# MCISO-S02-V00-PSU5VA.net
KiCad netlist of a schematic drawn in Altium Designer
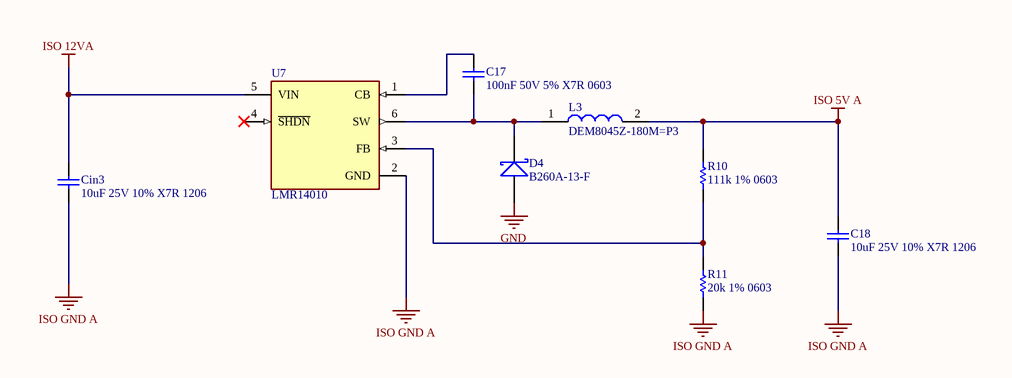
[diagram p0: MCISO-S02-V00-PSU5VA.SchDoc]

(export (version "E")
  (design (tool "Eeschema 10.0.6"))
  (components
    (comp (ref "C17")
      (value "100nF 50V 5% X7R 0603")
      (footprint "Cap_Ceramic_0603")
      (description "Capacitor, Ceramic, SMD, 100nF, 50V, 5%, X7R, 0603")
      (libsource (lib "QUTMS-MCISOLibrary") (part "100nF 50V 5% X7R 0603"))
    )
    (comp (ref "C18")
      (value "10uF 25V 10% X7R 1206")
      (footprint "Cap_Ceramic_1206")
      (description "Capacitor, Ceramic, SMD, 10uF, 25V, 10%, X7R, 1206")
      (libsource (lib "QUTMS-MCISOLibrary") (part "10uF 25V 10% X7R 1206"))
    )
    (comp (ref "Cin3")
      (value "10uF 25V 10% X7R 1206")
      (footprint "Cap_Ceramic_1206")
      (description "Capacitor, Ceramic, SMD, 10uF, 25V, 10%, X7R, 1206")
      (libsource (lib "StandardCapacitors") (part "10uF 25V 10% X7R 1206"))
    )
    (comp (ref "D4")
      (value "B260A-13-F")
      (footprint "SMA")
      (description "Diode, Schottky Barrier Rectifier, 60 V, 2 A, B260A-13-F")
      (libsource (lib "QUTMS-MCISOLibrary") (part "B260A-13-F"))
    )
    (comp (ref "L3")
      (value "DEM8045Z-180M=P3")
      (footprint "SamacSys:1217ASH100MP3")
      (description "Inductor")
      (fields (field (name "MOUSER PART NUMBER") "81-DEM8045Z-180M=P3"))
      (libsource (lib "QUTMS-MCISOLibrary") (part "DEM8045Z-180M=P3"))
    )
    (comp (ref "R10")
      (value "111k 1% 0603")
      (footprint "Res_ThinFilm_0603")
      (description "Resistor, SMD, 111k, 0.1W, 1%, 0603")
      (libsource (lib "QUTMS-MCISOLibrary") (part "111k 1% 0603"))
    )
    (comp (ref "R11")
      (value "20k 1% 0603")
      (footprint "Res_ThinFilm_0603")
      (description "Resistor, SMD, 20k, 0.1W, 5%, 0603")
      (libsource (lib "QUTMS-MCISOLibrary") (part "20k 1% 0603"))
    )
    (comp (ref "U7")
      (value "LMR14010")
      (footprint "LMR14010")
      (libsource (lib "QUTMS-MCISOLibrary") (part "LMR14010"))
    )
  )
  (nets
    (net (code "1") (name "GND") (class "Default")
      (node (ref "D4") (pin "A") (pinfunction "A_A") (pintype "passive"))
    )
    (net (code "2") (name "ISO 5V A") (class "Default")
      (node (ref "C18") (pin "2") (pinfunction "2_2") (pintype "passive"))
      (node (ref "L3") (pin "2") (pinfunction "2_2") (pintype "passive"))
      (node (ref "R10") (pin "2") (pinfunction "2_2") (pintype "passive"))
    )
    (net (code "3") (name "ISO 12VA") (class "Default")
      (node (ref "Cin3") (pin "2") (pinfunction "2_2") (pintype "passive"))
      (node (ref "U7") (pin "5") (pinfunction "VIN_5") (pintype "power_in"))
    )
    (net (code "4") (name "ISO GND A") (class "Default")
      (node (ref "C18") (pin "1") (pinfunction "1_1") (pintype "passive"))
      (node (ref "Cin3") (pin "1") (pinfunction "1_1") (pintype "passive"))
      (node (ref "R11") (pin "1") (pinfunction "1_1") (pintype "passive"))
      (node (ref "U7") (pin "2") (pinfunction "GND_2") (pintype "power_in"))
    )
    (net (code "5") (name "Net-(U7-CB)") (class "Default")
      (node (ref "C17") (pin "2") (pinfunction "2_2") (pintype "passive"))
      (node (ref "U7") (pin "1") (pinfunction "CB_1") (pintype "input"))
    )
    (net (code "6") (name "Net-(U7-FB)") (class "Default")
      (node (ref "R10") (pin "1") (pinfunction "1_1") (pintype "passive"))
      (node (ref "R11") (pin "2") (pinfunction "2_2") (pintype "passive"))
      (node (ref "U7") (pin "3") (pinfunction "FB_3") (pintype "input"))
    )
    (net (code "7") (name "Net-(U7-SW)") (class "Default")
      (node (ref "C17") (pin "1") (pinfunction "1_1") (pintype "passive"))
      (node (ref "D4") (pin "K") (pinfunction "K_K") (pintype "passive"))
      (node (ref "L3") (pin "1") (pinfunction "1_1") (pintype "passive"))
      (node (ref "U7") (pin "6") (pinfunction "SW_6") (pintype "output"))
    )
    (net (code "8") (name "unconnected-(U7-~{SHDN}-Pad4)") (class "Default")
      (node (ref "U7") (pin "4") (pinfunction "~{SHDN}_4") (pintype "input+no_connect"))
    )
  )
)
